# InPut.net
KiCad netlist of a schematic drawn in Altium Designer
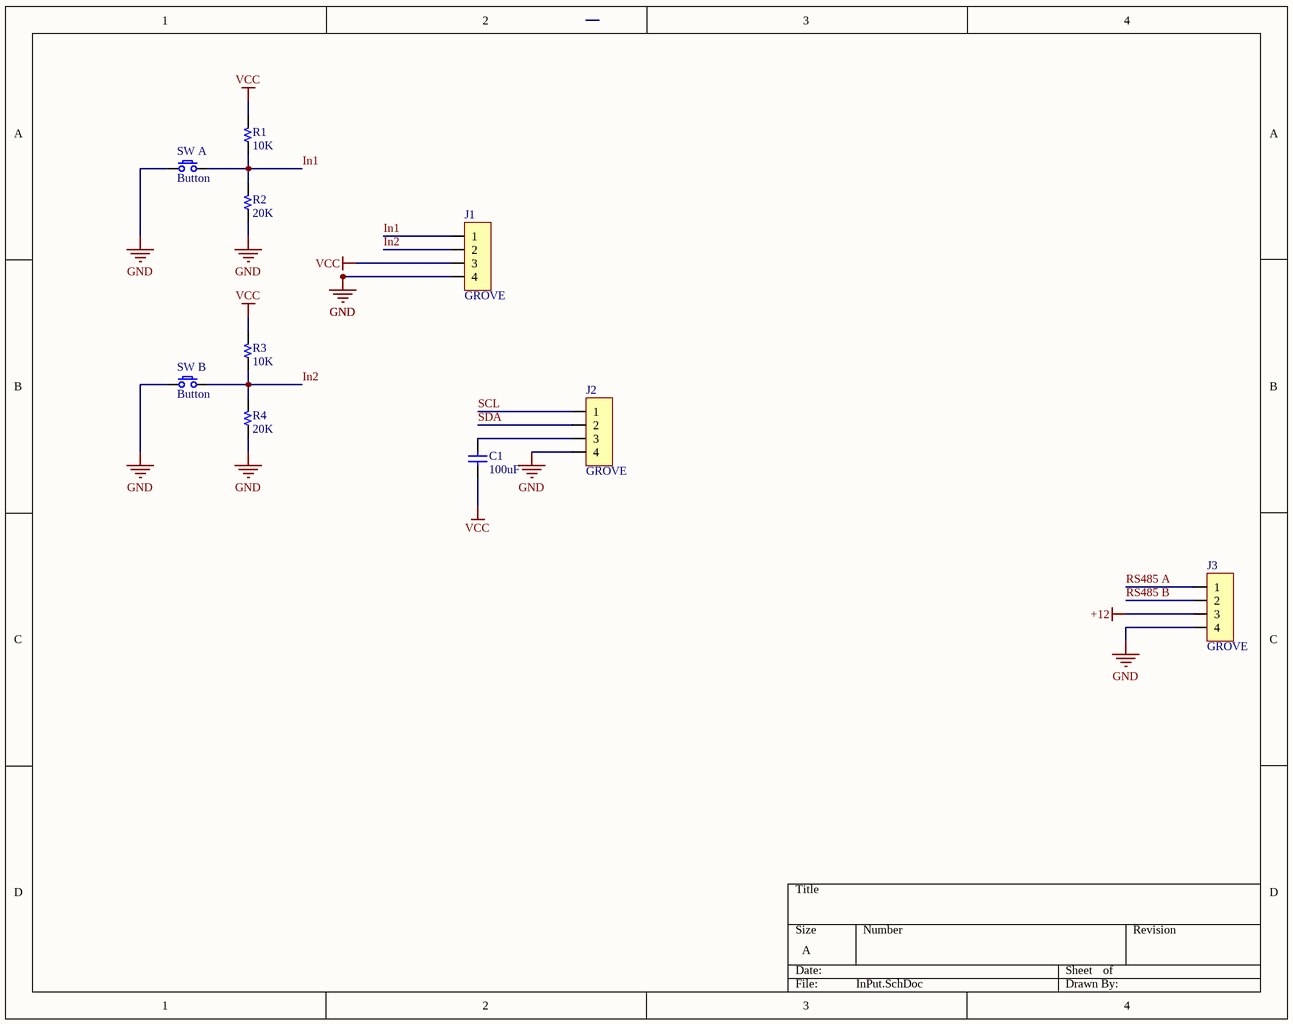
[diagram p0: InPut.SchDoc]

(export (version "E")
  (design (tool "Eeschema 10.0.6"))
  (components
    (comp (ref "C1")
      (value "100uF")
      (footprint "C 0805")
      (description "Capacitor non-pol")
      (libsource (lib "chipfc_altium_libs") (part "Capacitor NP"))
    )
    (comp (ref "J1")
      (value "GROVE")
      (footprint "HDR/Header/4/BOX/SMD")
      (description "Header, 4-Pin")
      (libsource (lib "chipfc_altium_libs") (part "Header 4"))
    )
    (comp (ref "J2")
      (value "GROVE")
      (footprint "HDR/Header/4/BOX/SMD")
      (description "Header, 4-Pin")
      (libsource (lib "chipfc_altium_libs") (part "Header 4"))
    )
    (comp (ref "J3")
      (value "GROVE")
      (footprint "HDR/Header/4/BOX/SMD")
      (description "Header, 4-Pin")
      (libsource (lib "chipfc_altium_libs") (part "Header 4"))
    )
    (comp (ref "R1")
      (value "10K")
      (footprint "R 0805")
      (description "Resistor")
      (libsource (lib "chipfc_altium_libs") (part "Resistor"))
    )
    (comp (ref "R2")
      (value "20K")
      (footprint "R 0805")
      (description "Resistor")
      (libsource (lib "chipfc_altium_libs") (part "Resistor"))
    )
    (comp (ref "R3")
      (value "10K")
      (footprint "R 0805")
      (description "Resistor")
      (libsource (lib "chipfc_altium_libs") (part "Resistor"))
    )
    (comp (ref "R4")
      (value "20K")
      (footprint "R 0805")
      (description "Resistor")
      (libsource (lib "chipfc_altium_libs") (part "Resistor"))
    )
    (comp (ref "SW A")
      (value "Button")
      (footprint "SW/2/DIP")
      (description "Tact switch 2 pin")
      (libsource (lib "chipfc_altium_libs") (part "SW SPST"))
    )
    (comp (ref "SW B")
      (value "Button")
      (footprint "SW/2/DIP")
      (description "Tact switch 2 pin")
      (libsource (lib "chipfc_altium_libs") (part "SW SPST"))
    )
  )
  (nets
    (net (code "1") (name "+12") (class "Default")
      (node (ref "J3") (pin "3") (pinfunction "3_3") (pintype "passive"))
    )
    (net (code "2") (name "/In1") (class "Default")
      (node (ref "J1") (pin "1") (pinfunction "1_1") (pintype "passive"))
      (node (ref "R1") (pin "1") (pinfunction "1_1") (pintype "passive"))
      (node (ref "R2") (pin "2") (pinfunction "2_2") (pintype "passive"))
      (node (ref "SW A") (pin "2") (pinfunction "2_2") (pintype "passive"))
    )
    (net (code "3") (name "/In2") (class "Default")
      (node (ref "J1") (pin "2") (pinfunction "2_2") (pintype "passive"))
      (node (ref "R3") (pin "1") (pinfunction "1_1") (pintype "passive"))
      (node (ref "R4") (pin "2") (pinfunction "2_2") (pintype "passive"))
      (node (ref "SW B") (pin "2") (pinfunction "2_2") (pintype "passive"))
    )
    (net (code "4") (name "/RS485 A") (class "Default")
      (node (ref "J3") (pin "1") (pinfunction "1_1") (pintype "passive"))
    )
    (net (code "5") (name "/RS485 B") (class "Default")
      (node (ref "J3") (pin "2") (pinfunction "2_2") (pintype "passive"))
    )
    (net (code "6") (name "/SCL") (class "Default")
      (node (ref "J2") (pin "1") (pinfunction "1_1") (pintype "passive"))
    )
    (net (code "7") (name "/SDA") (class "Default")
      (node (ref "J2") (pin "2") (pinfunction "2_2") (pintype "passive"))
    )
    (net (code "8") (name "GND") (class "Default")
      (node (ref "J1") (pin "4") (pinfunction "4_4") (pintype "passive"))
      (node (ref "J2") (pin "4") (pinfunction "4_4") (pintype "passive"))
      (node (ref "J3") (pin "4") (pinfunction "4_4") (pintype "passive"))
      (node (ref "R2") (pin "1") (pinfunction "1_1") (pintype "passive"))
      (node (ref "R4") (pin "1") (pinfunction "1_1") (pintype "passive"))
      (node (ref "SW A") (pin "1") (pinfunction "1_1") (pintype "passive"))
      (node (ref "SW B") (pin "1") (pinfunction "1_1") (pintype "passive"))
    )
    (net (code "9") (name "Net-(C1-Pad1)") (class "Default")
      (node (ref "C1") (pin "1") (pinfunction "1_1") (pintype "passive"))
      (node (ref "J2") (pin "3") (pinfunction "3_3") (pintype "passive"))
    )
    (net (code "10") (name "VCC") (class "Default")
      (node (ref "C1") (pin "2") (pinfunction "2_2") (pintype "passive"))
      (node (ref "J1") (pin "3") (pinfunction "3_3") (pintype "passive"))
      (node (ref "R1") (pin "2") (pinfunction "2_2") (pintype "passive"))
      (node (ref "R3") (pin "2") (pinfunction "2_2") (pintype "passive"))
    )
  )
)
